# Orbiter_V2.net
KiCad netlist of a schematic drawn in EAGLE
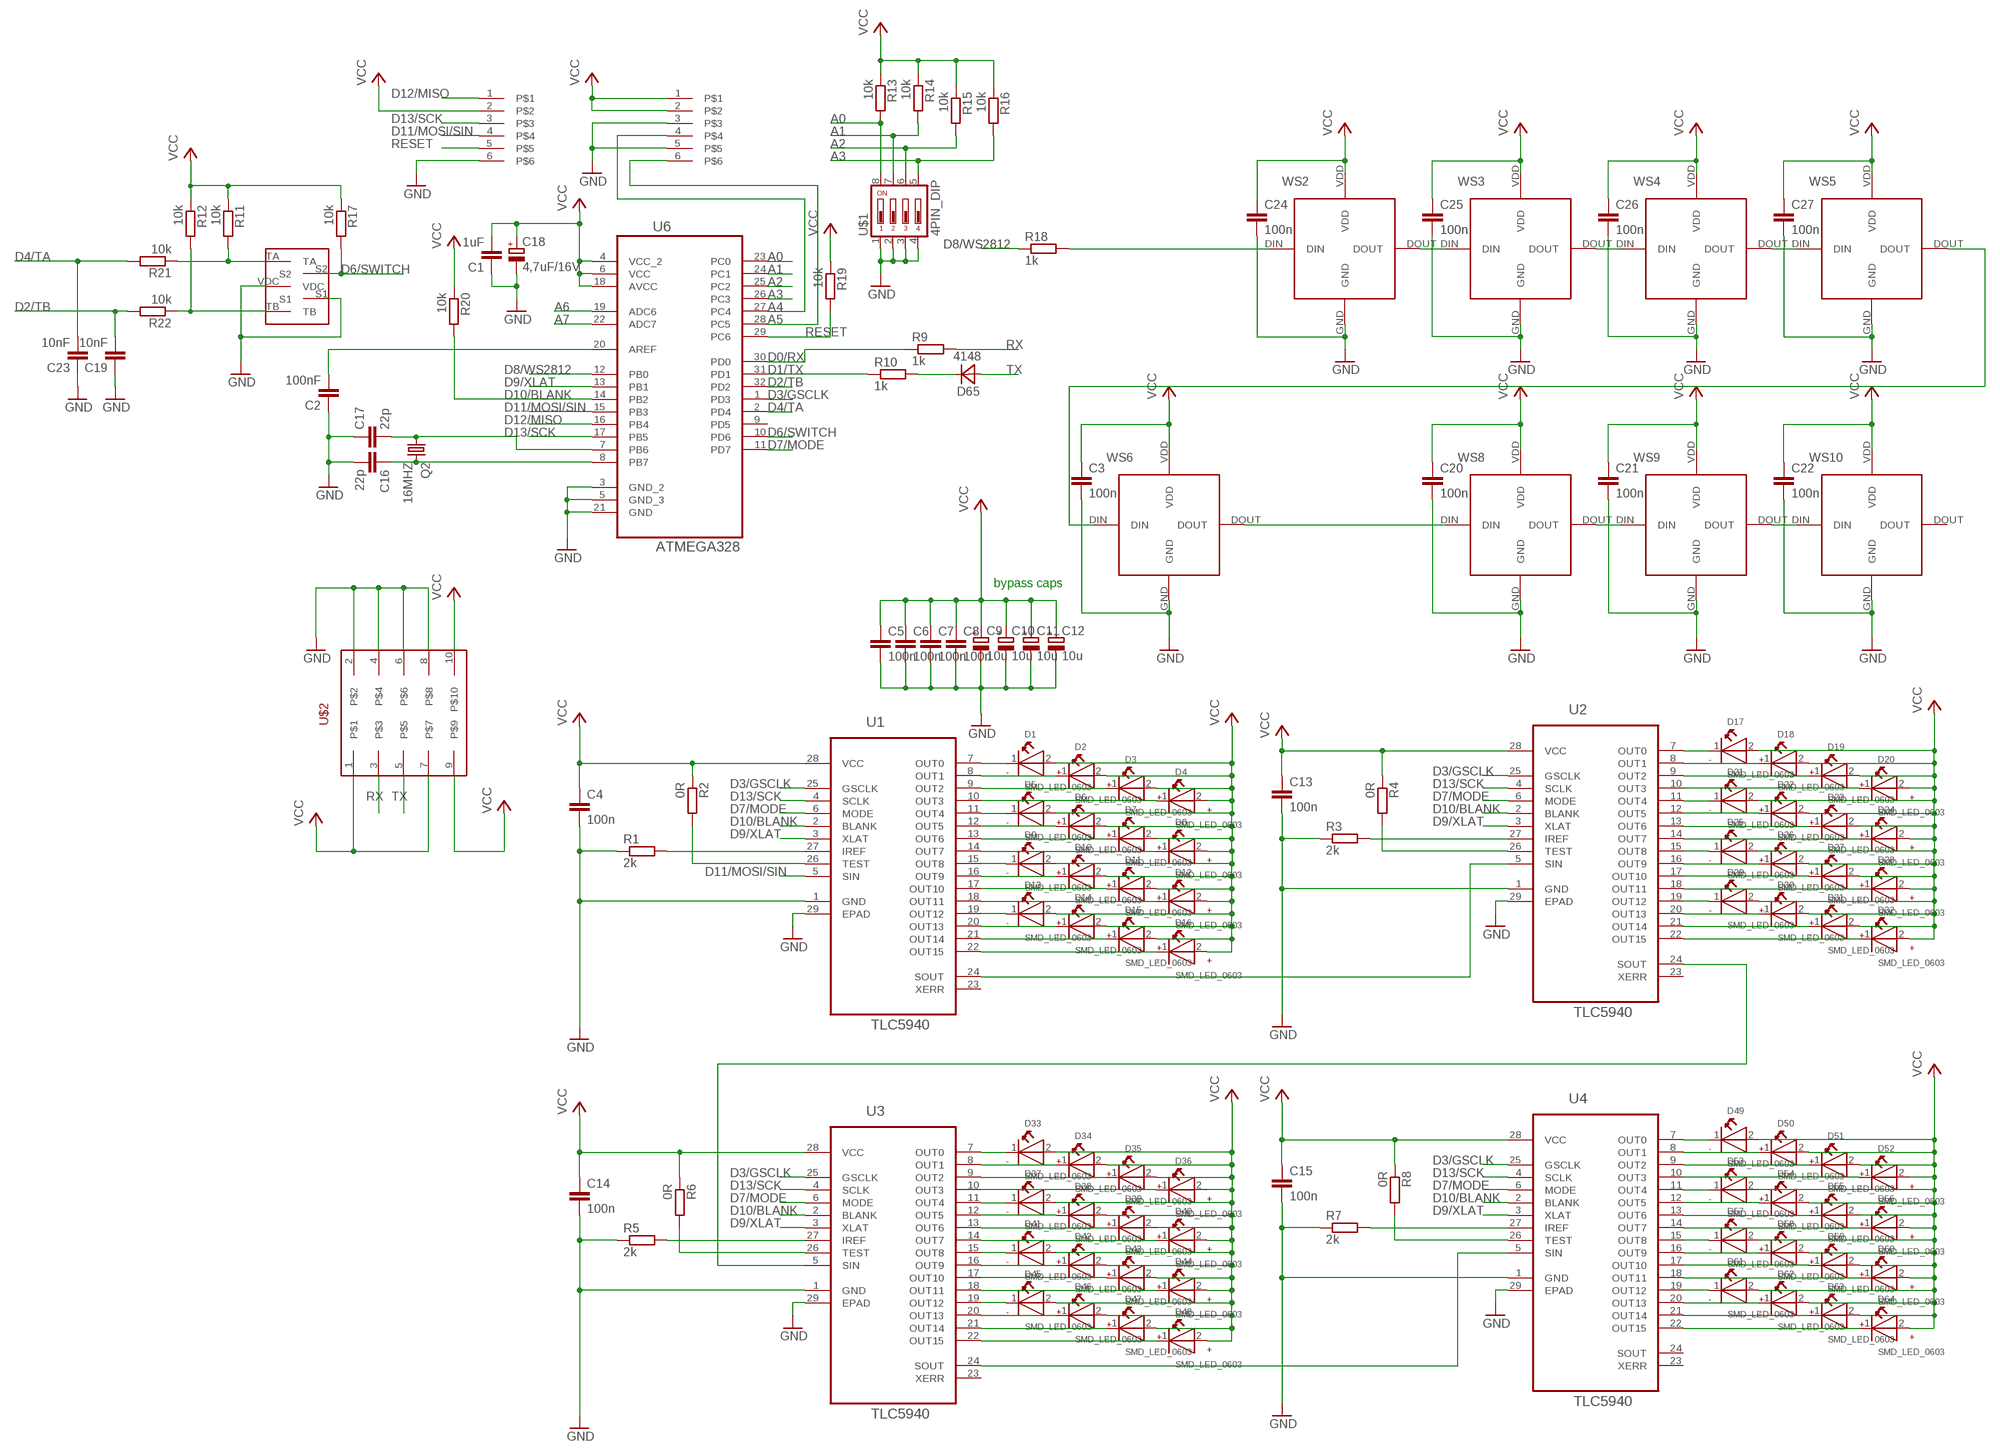
[diagram p0: schematic, sheet 1]

(export (version "E")
  (design (tool "Eeschema 10.0.6"))
  (components
    (comp (ref "C1")
      (value "1uF")
      (footprint "eagle-import:C0603")
      (libsource (lib "eagle-import") (part "KONDENSATOR_0603"))
    )
    (comp (ref "C2")
      (value "100nF")
      (footprint "eagle-import:C0603")
      (libsource (lib "eagle-import") (part "KONDENSATOR_0603"))
    )
    (comp (ref "C3")
      (value "100n")
      (footprint "eagle-import:C0603")
      (libsource (lib "eagle-import") (part "KONDENSATOR_0603"))
    )
    (comp (ref "C4")
      (value "100n")
      (footprint "eagle-import:C0603")
      (libsource (lib "eagle-import") (part "KONDENSATOR_0603"))
    )
    (comp (ref "C5")
      (value "100n")
      (footprint "eagle-import:C0603")
      (libsource (lib "eagle-import") (part "KONDENSATOR_0603"))
    )
    (comp (ref "C6")
      (value "100n")
      (footprint "eagle-import:C0603")
      (libsource (lib "eagle-import") (part "KONDENSATOR_0603"))
    )
    (comp (ref "C7")
      (value "100n")
      (footprint "eagle-import:C0603")
      (libsource (lib "eagle-import") (part "KONDENSATOR_0603"))
    )
    (comp (ref "C8")
      (value "100n")
      (footprint "eagle-import:C0603")
      (libsource (lib "eagle-import") (part "KONDENSATOR_0603"))
    )
    (comp (ref "C9")
      (value "10u")
      (footprint "eagle-import:153CLV-0605")
      (libsource (lib "eagle-import") (part "SMD_ELCTROLYTIC"))
    )
    (comp (ref "C10")
      (value "10u")
      (footprint "eagle-import:153CLV-0605")
      (libsource (lib "eagle-import") (part "SMD_ELCTROLYTIC"))
    )
    (comp (ref "C11")
      (value "10u")
      (footprint "eagle-import:153CLV-0605")
      (libsource (lib "eagle-import") (part "SMD_ELCTROLYTIC"))
    )
    (comp (ref "C12")
      (value "10u")
      (footprint "eagle-import:153CLV-0605")
      (libsource (lib "eagle-import") (part "SMD_ELCTROLYTIC"))
    )
    (comp (ref "C13")
      (value "100n")
      (footprint "eagle-import:C0603")
      (libsource (lib "eagle-import") (part "KONDENSATOR_0603"))
    )
    (comp (ref "C14")
      (value "100n")
      (footprint "eagle-import:C0603")
      (libsource (lib "eagle-import") (part "KONDENSATOR_0603"))
    )
    (comp (ref "C15")
      (value "100n")
      (footprint "eagle-import:C0603")
      (libsource (lib "eagle-import") (part "KONDENSATOR_0603"))
    )
    (comp (ref "C16")
      (value "22p")
      (footprint "eagle-import:C0603")
      (libsource (lib "eagle-import") (part "KONDENSATOR_0603"))
    )
    (comp (ref "C17")
      (value "22p")
      (footprint "eagle-import:C0603")
      (libsource (lib "eagle-import") (part "KONDENSATOR_0603"))
    )
    (comp (ref "C18")
      (value "4,7uF/16V")
      (footprint "eagle-import:153CLV-0605")
      (libsource (lib "eagle-import") (part "SMD_ELCTROLYTIC"))
    )
    (comp (ref "C19")
      (value "10nF")
      (footprint "eagle-import:C0603")
      (libsource (lib "eagle-import") (part "KONDENSATOR_0603"))
    )
    (comp (ref "C20")
      (value "100n")
      (footprint "eagle-import:C0603")
      (libsource (lib "eagle-import") (part "KONDENSATOR_0603"))
    )
    (comp (ref "C21")
      (value "100n")
      (footprint "eagle-import:C0603")
      (libsource (lib "eagle-import") (part "KONDENSATOR_0603"))
    )
    (comp (ref "C22")
      (value "100n")
      (footprint "eagle-import:C0603")
      (libsource (lib "eagle-import") (part "KONDENSATOR_0603"))
    )
    (comp (ref "C23")
      (value "10nF")
      (footprint "eagle-import:C0603")
      (libsource (lib "eagle-import") (part "KONDENSATOR_0603"))
    )
    (comp (ref "C24")
      (value "100n")
      (footprint "eagle-import:C0603")
      (libsource (lib "eagle-import") (part "KONDENSATOR_0603"))
    )
    (comp (ref "C25")
      (value "100n")
      (footprint "eagle-import:C0603")
      (libsource (lib "eagle-import") (part "KONDENSATOR_0603"))
    )
    (comp (ref "C26")
      (value "100n")
      (footprint "eagle-import:C0603")
      (libsource (lib "eagle-import") (part "KONDENSATOR_0603"))
    )
    (comp (ref "C27")
      (value "100n")
      (footprint "eagle-import:C0603")
      (libsource (lib "eagle-import") (part "KONDENSATOR_0603"))
    )
    (comp (ref "D1")
      (value "SMD_LED_0603")
      (footprint "eagle-import:WL-SMCW_0603")
      (libsource (lib "eagle-import") (part "SMD_LED_0603"))
    )
    (comp (ref "D2")
      (value "SMD_LED_0603")
      (footprint "eagle-import:WL-SMCW_0603")
      (libsource (lib "eagle-import") (part "SMD_LED_0603"))
    )
    (comp (ref "D3")
      (value "SMD_LED_0603")
      (footprint "eagle-import:WL-SMCW_0603")
      (libsource (lib "eagle-import") (part "SMD_LED_0603"))
    )
    (comp (ref "D4")
      (value "SMD_LED_0603")
      (footprint "eagle-import:WL-SMCW_0603")
      (libsource (lib "eagle-import") (part "SMD_LED_0603"))
    )
    (comp (ref "D5")
      (value "SMD_LED_0603")
      (footprint "eagle-import:WL-SMCW_0603")
      (libsource (lib "eagle-import") (part "SMD_LED_0603"))
    )
    (comp (ref "D6")
      (value "SMD_LED_0603")
      (footprint "eagle-import:WL-SMCW_0603")
      (libsource (lib "eagle-import") (part "SMD_LED_0603"))
    )
    (comp (ref "D7")
      (value "SMD_LED_0603")
      (footprint "eagle-import:WL-SMCW_0603")
      (libsource (lib "eagle-import") (part "SMD_LED_0603"))
    )
    (comp (ref "D8")
      (value "SMD_LED_0603")
      (footprint "eagle-import:WL-SMCW_0603")
      (libsource (lib "eagle-import") (part "SMD_LED_0603"))
    )
    (comp (ref "D9")
      (value "SMD_LED_0603")
      (footprint "eagle-import:WL-SMCW_0603")
      (libsource (lib "eagle-import") (part "SMD_LED_0603"))
    )
    (comp (ref "D10")
      (value "SMD_LED_0603")
      (footprint "eagle-import:WL-SMCW_0603")
      (libsource (lib "eagle-import") (part "SMD_LED_0603"))
    )
    (comp (ref "D11")
      (value "SMD_LED_0603")
      (footprint "eagle-import:WL-SMCW_0603")
      (libsource (lib "eagle-import") (part "SMD_LED_0603"))
    )
    (comp (ref "D12")
      (value "SMD_LED_0603")
      (footprint "eagle-import:WL-SMCW_0603")
      (libsource (lib "eagle-import") (part "SMD_LED_0603"))
    )
    (comp (ref "D13")
      (value "SMD_LED_0603")
      (footprint "eagle-import:WL-SMCW_0603")
      (libsource (lib "eagle-import") (part "SMD_LED_0603"))
    )
    (comp (ref "D14")
      (value "SMD_LED_0603")
      (footprint "eagle-import:WL-SMCW_0603")
      (libsource (lib "eagle-import") (part "SMD_LED_0603"))
    )
    (comp (ref "D15")
      (value "SMD_LED_0603")
      (footprint "eagle-import:WL-SMCW_0603")
      (libsource (lib "eagle-import") (part "SMD_LED_0603"))
    )
    (comp (ref "D16")
      (value "SMD_LED_0603")
      (footprint "eagle-import:WL-SMCW_0603")
      (libsource (lib "eagle-import") (part "SMD_LED_0603"))
    )
    (comp (ref "D17")
      (value "SMD_LED_0603")
      (footprint "eagle-import:WL-SMCW_0603")
      (libsource (lib "eagle-import") (part "SMD_LED_0603"))
    )
    (comp (ref "D18")
      (value "SMD_LED_0603")
      (footprint "eagle-import:WL-SMCW_0603")
      (libsource (lib "eagle-import") (part "SMD_LED_0603"))
    )
    (comp (ref "D19")
      (value "SMD_LED_0603")
      (footprint "eagle-import:WL-SMCW_0603")
      (libsource (lib "eagle-import") (part "SMD_LED_0603"))
    )
    (comp (ref "D20")
      (value "SMD_LED_0603")
      (footprint "eagle-import:WL-SMCW_0603")
      (libsource (lib "eagle-import") (part "SMD_LED_0603"))
    )
    (comp (ref "D21")
      (value "SMD_LED_0603")
      (footprint "eagle-import:WL-SMCW_0603")
      (libsource (lib "eagle-import") (part "SMD_LED_0603"))
    )
    (comp (ref "D22")
      (value "SMD_LED_0603")
      (footprint "eagle-import:WL-SMCW_0603")
      (libsource (lib "eagle-import") (part "SMD_LED_0603"))
    )
    (comp (ref "D23")
      (value "SMD_LED_0603")
      (footprint "eagle-import:WL-SMCW_0603")
      (libsource (lib "eagle-import") (part "SMD_LED_0603"))
    )
    (comp (ref "D24")
      (value "SMD_LED_0603")
      (footprint "eagle-import:WL-SMCW_0603")
      (libsource (lib "eagle-import") (part "SMD_LED_0603"))
    )
    (comp (ref "D25")
      (value "SMD_LED_0603")
      (footprint "eagle-import:WL-SMCW_0603")
      (libsource (lib "eagle-import") (part "SMD_LED_0603"))
    )
    (comp (ref "D26")
      (value "SMD_LED_0603")
      (footprint "eagle-import:WL-SMCW_0603")
      (libsource (lib "eagle-import") (part "SMD_LED_0603"))
    )
    (comp (ref "D27")
      (value "SMD_LED_0603")
      (footprint "eagle-import:WL-SMCW_0603")
      (libsource (lib "eagle-import") (part "SMD_LED_0603"))
    )
    (comp (ref "D28")
      (value "SMD_LED_0603")
      (footprint "eagle-import:WL-SMCW_0603")
      (libsource (lib "eagle-import") (part "SMD_LED_0603"))
    )
    (comp (ref "D29")
      (value "SMD_LED_0603")
      (footprint "eagle-import:WL-SMCW_0603")
      (libsource (lib "eagle-import") (part "SMD_LED_0603"))
    )
    (comp (ref "D30")
      (value "SMD_LED_0603")
      (footprint "eagle-import:WL-SMCW_0603")
      (libsource (lib "eagle-import") (part "SMD_LED_0603"))
    )
    (comp (ref "D31")
      (value "SMD_LED_0603")
      (footprint "eagle-import:WL-SMCW_0603")
      (libsource (lib "eagle-import") (part "SMD_LED_0603"))
    )
    (comp (ref "D32")
      (value "SMD_LED_0603")
      (footprint "eagle-import:WL-SMCW_0603")
      (libsource (lib "eagle-import") (part "SMD_LED_0603"))
    )
    (comp (ref "D33")
      (value "SMD_LED_0603")
      (footprint "eagle-import:WL-SMCW_0603")
      (libsource (lib "eagle-import") (part "SMD_LED_0603"))
    )
    (comp (ref "D34")
      (value "SMD_LED_0603")
      (footprint "eagle-import:WL-SMCW_0603")
      (libsource (lib "eagle-import") (part "SMD_LED_0603"))
    )
    (comp (ref "D35")
      (value "SMD_LED_0603")
      (footprint "eagle-import:WL-SMCW_0603")
      (libsource (lib "eagle-import") (part "SMD_LED_0603"))
    )
    (comp (ref "D36")
      (value "SMD_LED_0603")
      (footprint "eagle-import:WL-SMCW_0603")
      (libsource (lib "eagle-import") (part "SMD_LED_0603"))
    )
    (comp (ref "D37")
      (value "SMD_LED_0603")
      (footprint "eagle-import:WL-SMCW_0603")
      (libsource (lib "eagle-import") (part "SMD_LED_0603"))
    )
    (comp (ref "D38")
      (value "SMD_LED_0603")
      (footprint "eagle-import:WL-SMCW_0603")
      (libsource (lib "eagle-import") (part "SMD_LED_0603"))
    )
    (comp (ref "D39")
      (value "SMD_LED_0603")
      (footprint "eagle-import:WL-SMCW_0603")
      (libsource (lib "eagle-import") (part "SMD_LED_0603"))
    )
    (comp (ref "D40")
      (value "SMD_LED_0603")
      (footprint "eagle-import:WL-SMCW_0603")
      (libsource (lib "eagle-import") (part "SMD_LED_0603"))
    )
    (comp (ref "D41")
      (value "SMD_LED_0603")
      (footprint "eagle-import:WL-SMCW_0603")
      (libsource (lib "eagle-import") (part "SMD_LED_0603"))
    )
    (comp (ref "D42")
      (value "SMD_LED_0603")
      (footprint "eagle-import:WL-SMCW_0603")
      (libsource (lib "eagle-import") (part "SMD_LED_0603"))
    )
    (comp (ref "D43")
      (value "SMD_LED_0603")
      (footprint "eagle-import:WL-SMCW_0603")
      (libsource (lib "eagle-import") (part "SMD_LED_0603"))
    )
    (comp (ref "D44")
      (value "SMD_LED_0603")
      (footprint "eagle-import:WL-SMCW_0603")
      (libsource (lib "eagle-import") (part "SMD_LED_0603"))
    )
    (comp (ref "D45")
      (value "SMD_LED_0603")
      (footprint "eagle-import:WL-SMCW_0603")
      (libsource (lib "eagle-import") (part "SMD_LED_0603"))
    )
    (comp (ref "D46")
      (value "SMD_LED_0603")
      (footprint "eagle-import:WL-SMCW_0603")
      (libsource (lib "eagle-import") (part "SMD_LED_0603"))
    )
    (comp (ref "D47")
      (value "SMD_LED_0603")
      (footprint "eagle-import:WL-SMCW_0603")
      (libsource (lib "eagle-import") (part "SMD_LED_0603"))
    )
    (comp (ref "D48")
      (value "SMD_LED_0603")
      (footprint "eagle-import:WL-SMCW_0603")
      (libsource (lib "eagle-import") (part "SMD_LED_0603"))
    )
    (comp (ref "D49")
      (value "SMD_LED_0603")
      (footprint "eagle-import:WL-SMCW_0603")
      (libsource (lib "eagle-import") (part "SMD_LED_0603"))
    )
    (comp (ref "D50")
      (value "SMD_LED_0603")
      (footprint "eagle-import:WL-SMCW_0603")
      (libsource (lib "eagle-import") (part "SMD_LED_0603"))
    )
    (comp (ref "D51")
      (value "SMD_LED_0603")
      (footprint "eagle-import:WL-SMCW_0603")
      (libsource (lib "eagle-import") (part "SMD_LED_0603"))
    )
    (comp (ref "D52")
      (value "SMD_LED_0603")
      (footprint "eagle-import:WL-SMCW_0603")
      (libsource (lib "eagle-import") (part "SMD_LED_0603"))
    )
    (comp (ref "D53")
      (value "SMD_LED_0603")
      (footprint "eagle-import:WL-SMCW_0603")
      (libsource (lib "eagle-import") (part "SMD_LED_0603"))
    )
    (comp (ref "D54")
      (value "SMD_LED_0603")
      (footprint "eagle-import:WL-SMCW_0603")
      (libsource (lib "eagle-import") (part "SMD_LED_0603"))
    )
    (comp (ref "D55")
      (value "SMD_LED_0603")
      (footprint "eagle-import:WL-SMCW_0603")
      (libsource (lib "eagle-import") (part "SMD_LED_0603"))
    )
    (comp (ref "D56")
      (value "SMD_LED_0603")
      (footprint "eagle-import:WL-SMCW_0603")
      (libsource (lib "eagle-import") (part "SMD_LED_0603"))
    )
    (comp (ref "D57")
      (value "SMD_LED_0603")
      (footprint "eagle-import:WL-SMCW_0603")
      (libsource (lib "eagle-import") (part "SMD_LED_0603"))
    )
    (comp (ref "D58")
      (value "SMD_LED_0603")
      (footprint "eagle-import:WL-SMCW_0603")
      (libsource (lib "eagle-import") (part "SMD_LED_0603"))
    )
    (comp (ref "D59")
      (value "SMD_LED_0603")
      (footprint "eagle-import:WL-SMCW_0603")
      (libsource (lib "eagle-import") (part "SMD_LED_0603"))
    )
    (comp (ref "D60")
      (value "SMD_LED_0603")
      (footprint "eagle-import:WL-SMCW_0603")
      (libsource (lib "eagle-import") (part "SMD_LED_0603"))
    )
    (comp (ref "D61")
      (value "SMD_LED_0603")
      (footprint "eagle-import:WL-SMCW_0603")
      (libsource (lib "eagle-import") (part "SMD_LED_0603"))
    )
    (comp (ref "D62")
      (value "SMD_LED_0603")
      (footprint "eagle-import:WL-SMCW_0603")
      (libsource (lib "eagle-import") (part "SMD_LED_0603"))
    )
    (comp (ref "D63")
      (value "SMD_LED_0603")
      (footprint "eagle-import:WL-SMCW_0603")
      (libsource (lib "eagle-import") (part "SMD_LED_0603"))
    )
    (comp (ref "D64")
      (value "SMD_LED_0603")
      (footprint "eagle-import:WL-SMCW_0603")
      (libsource (lib "eagle-import") (part "SMD_LED_0603"))
    )
    (comp (ref "D65")
      (value "4148")
      (footprint "eagle-import:SOD323-R")
      (libsource (lib "eagle-import") (part "4148_SOD323"))
    )
    (comp (ref "Q2")
      (value "16MHZ")
      (footprint "eagle-import:SM49")
      (libsource (lib "eagle-import") (part "CRYSTAL_SM49"))
    )
    (comp (ref "R1")
      (value "2k")
      (footprint "eagle-import:R0805")
      (libsource (lib "eagle-import") (part "WIDERSTAND_0805R0805"))
    )
    (comp (ref "R2")
      (value "0R")
      (footprint "eagle-import:R0805")
      (libsource (lib "eagle-import") (part "WIDERSTAND_0805R0805"))
    )
    (comp (ref "R3")
      (value "2k")
      (footprint "eagle-import:R0805")
      (libsource (lib "eagle-import") (part "WIDERSTAND_0805R0805"))
    )
    (comp (ref "R4")
      (value "0R")
      (footprint "eagle-import:R0805")
      (libsource (lib "eagle-import") (part "WIDERSTAND_0805R0805"))
    )
    (comp (ref "R5")
      (value "2k")
      (footprint "eagle-import:R0805")
      (libsource (lib "eagle-import") (part "WIDERSTAND_0805R0805"))
    )
    (comp (ref "R6")
      (value "0R")
      (footprint "eagle-import:R0805")
      (libsource (lib "eagle-import") (part "WIDERSTAND_0805R0805"))
    )
    (comp (ref "R7")
      (value "2k")
      (footprint "eagle-import:R0805")
      (libsource (lib "eagle-import") (part "WIDERSTAND_0805R0805"))
    )
    (comp (ref "R8")
      (value "0R")
      (footprint "eagle-import:R0805")
      (libsource (lib "eagle-import") (part "WIDERSTAND_0805R0805"))
    )
    (comp (ref "R9")
      (value "1k")
      (footprint "eagle-import:R0805")
      (libsource (lib "eagle-import") (part "WIDERSTAND_0805R0805"))
    )
    (comp (ref "R10")
      (value "1k")
      (footprint "eagle-import:R0805")
      (libsource (lib "eagle-import") (part "WIDERSTAND_0805R0805"))
    )
    (comp (ref "R11")
      (value "10k")
      (footprint "eagle-import:R0805")
      (libsource (lib "eagle-import") (part "WIDERSTAND_0805R0805"))
    )
    (comp (ref "R12")
      (value "10k")
      (footprint "eagle-import:R0805")
      (libsource (lib "eagle-import") (part "WIDERSTAND_0805R0805"))
    )
    (comp (ref "R13")
      (value "10k")
      (footprint "eagle-import:R0805")
      (libsource (lib "eagle-import") (part "WIDERSTAND_0805R0805"))
    )
    (comp (ref "R14")
      (value "10k")
      (footprint "eagle-import:R0805")
      (libsource (lib "eagle-import") (part "WIDERSTAND_0805R0805"))
    )
    (comp (ref "R15")
      (value "10k")
      (footprint "eagle-import:R0805")
      (libsource (lib "eagle-import") (part "WIDERSTAND_0805R0805"))
    )
    (comp (ref "R16")
      (value "10k")
      (footprint "eagle-import:R0805")
      (libsource (lib "eagle-import") (part "WIDERSTAND_0805R0805"))
    )
    (comp (ref "R17")
      (value "10k")
      (footprint "eagle-import:R0805")
      (libsource (lib "eagle-import") (part "WIDERSTAND_0805R0805"))
    )
    (comp (ref "R18")
      (value "1k")
      (footprint "eagle-import:R0805")
      (libsource (lib "eagle-import") (part "WIDERSTAND_0805R0805"))
    )
    (comp (ref "R19")
      (value "10k")
      (footprint "eagle-import:R0805")
      (libsource (lib "eagle-import") (part "WIDERSTAND_0805R0805"))
    )
    (comp (ref "R20")
      (value "10k")
      (footprint "eagle-import:R0805")
      (libsource (lib "eagle-import") (part "WIDERSTAND_0805R0805"))
    )
    (comp (ref "R21")
      (value "10k")
      (footprint "eagle-import:R0805")
      (libsource (lib "eagle-import") (part "WIDERSTAND_0805R0805"))
    )
    (comp (ref "R22")
      (value "10k")
      (footprint "eagle-import:R0805")
      (libsource (lib "eagle-import") (part "WIDERSTAND_0805R0805"))
    )
    (comp (ref "U$1")
      (value "4PIN_DIP")
      (footprint "eagle-import:CTS-219-04")
      (libsource (lib "eagle-import") (part "4PIN_DIP"))
    )
    (comp (ref "U$2")
      (value "10PIN_HEADER_SMD")
      (footprint "eagle-import:87832-10")
      (libsource (lib "eagle-import") (part "10PIN_HEADER_SMD"))
    )
    (comp (ref "U$3")
      (value "6PIN_HEADER_SMD_OPEN")
      (footprint "eagle-import:6PIN_HEADER_SMD_OPEN")
      (libsource (lib "eagle-import") (part "6PIN_HEADER_SMD_OPEN"))
    )
    (comp (ref "U$4")
      (value "BOURNS_ENCODER")
      (footprint "eagle-import:BOURNS_ENCODER_SMD")
      (libsource (lib "eagle-import") (part "BOURNS_ENCODER"))
    )
    (comp (ref "U$5")
      (value "6PIN_HEADER_SMD_OPEN")
      (footprint "eagle-import:6PIN_HEADER_SMD_OPEN")
      (libsource (lib "eagle-import") (part "6PIN_HEADER_SMD_OPEN"))
    )
    (comp (ref "U1")
      (value "TLC5940")
      (footprint "eagle-import:SOP65P640X120-29N")
      (fields (field (name "MPN") "TLC59401PWP"))
      (libsource (lib "eagle-import") (part "TLC59401PWP"))
    )
    (comp (ref "U2")
      (value "TLC5940")
      (footprint "eagle-import:SOP65P640X120-29N")
      (fields (field (name "MPN") "TLC59401PWP"))
      (libsource (lib "eagle-import") (part "TLC59401PWP"))
    )
    (comp (ref "U3")
      (value "TLC5940")
      (footprint "eagle-import:SOP65P640X120-29N")
      (fields (field (name "MPN") "TLC59401PWP"))
      (libsource (lib "eagle-import") (part "TLC59401PWP"))
    )
    (comp (ref "U4")
      (value "TLC5940")
      (footprint "eagle-import:SOP65P640X120-29N")
      (fields (field (name "MPN") "TLC59401PWP"))
      (libsource (lib "eagle-import") (part "TLC59401PWP"))
    )
    (comp (ref "U6")
      (value "ATMEGA328")
      (footprint "eagle-import:QFP80P900X900X120-32N")
      (fields (field (name "MPN") "ATMEGA328P-AU"))
      (libsource (lib "eagle-import") (part "ATMEGA328P-AU"))
    )
    (comp (ref "WS2")
      (value "WS2812")
      (footprint "eagle-import:WS2812")
      (libsource (lib "eagle-import") (part "WS2812"))
    )
    (comp (ref "WS3")
      (value "WS2812")
      (footprint "eagle-import:WS2812")
      (libsource (lib "eagle-import") (part "WS2812"))
    )
    (comp (ref "WS4")
      (value "WS2812")
      (footprint "eagle-import:WS2812")
      (libsource (lib "eagle-import") (part "WS2812"))
    )
    (comp (ref "WS5")
      (value "WS2812")
      (footprint "eagle-import:WS2812")
      (libsource (lib "eagle-import") (part "WS2812"))
    )
    (comp (ref "WS6")
      (value "WS2812")
      (footprint "eagle-import:WS2812")
      (libsource (lib "eagle-import") (part "WS2812"))
    )
    (comp (ref "WS8")
      (value "WS2812")
      (footprint "eagle-import:WS2812")
      (libsource (lib "eagle-import") (part "WS2812"))
    )
    (comp (ref "WS9")
      (value "WS2812")
      (footprint "eagle-import:WS2812")
      (libsource (lib "eagle-import") (part "WS2812"))
    )
    (comp (ref "WS10")
      (value "WS2812")
      (footprint "eagle-import:WS2812")
      (libsource (lib "eagle-import") (part "WS2812"))
    )
  )
  (nets
    (net (code "1") (name "/A0") (class "Default")
      (node (ref "R13") (pin "2") (pinfunction "2_2") (pintype "passive"))
      (node (ref "U$1") (pin "8") (pinfunction "8_8") (pintype "passive"))
      (node (ref "U6") (pin "23") (pinfunction "PC0_23") (pintype "bidirectional"))
    )
    (net (code "2") (name "/A1") (class "Default")
      (node (ref "R14") (pin "2") (pinfunction "2_2") (pintype "passive"))
      (node (ref "U$1") (pin "7") (pinfunction "7_7") (pintype "passive"))
      (node (ref "U6") (pin "24") (pinfunction "PC1_24") (pintype "bidirectional"))
    )
    (net (code "3") (name "/A2") (class "Default")
      (node (ref "R15") (pin "2") (pinfunction "2_2") (pintype "passive"))
      (node (ref "U$1") (pin "6") (pinfunction "6_6") (pintype "passive"))
      (node (ref "U6") (pin "25") (pinfunction "PC2_25") (pintype "bidirectional"))
    )
    (net (code "4") (name "/A3") (class "Default")
      (node (ref "R16") (pin "2") (pinfunction "2_2") (pintype "passive"))
      (node (ref "U$1") (pin "5") (pinfunction "5_5") (pintype "passive"))
      (node (ref "U6") (pin "26") (pinfunction "PC3_26") (pintype "bidirectional"))
    )
    (net (code "5") (name "/A4") (class "Default")
      (node (ref "U$5") (pin "4") (pinfunction "P$4_4") (pintype "bidirectional"))
      (node (ref "U6") (pin "27") (pinfunction "PC4_27") (pintype "bidirectional"))
    )
    (net (code "6") (name "/A5") (class "Default")
      (node (ref "U$5") (pin "6") (pinfunction "P$6_6") (pintype "bidirectional"))
      (node (ref "U6") (pin "28") (pinfunction "PC5_28") (pintype "bidirectional"))
    )
    (net (code "7") (name "/A6") (class "Default")
      (node (ref "U6") (pin "19") (pinfunction "ADC6_19") (pintype "input"))
    )
    (net (code "8") (name "/A7") (class "Default")
      (node (ref "U6") (pin "22") (pinfunction "ADC7_22") (pintype "input"))
    )
    (net (code "9") (name "/D0{slash}RX") (class "Default")
      (node (ref "R9") (pin "1") (pinfunction "1_1") (pintype "passive"))
      (node (ref "U6") (pin "30") (pinfunction "PD0_30") (pintype "bidirectional"))
    )
    (net (code "10") (name "/D1{slash}TX") (class "Default")
      (node (ref "R10") (pin "1") (pinfunction "1_1") (pintype "passive"))
      (node (ref "U6") (pin "31") (pinfunction "PD1_31") (pintype "bidirectional"))
    )
    (net (code "11") (name "/D2{slash}TB") (class "Default")
      (node (ref "C19") (pin "2") (pinfunction "2_2") (pintype "passive"))
      (node (ref "R22") (pin "2") (pinfunction "2_2") (pintype "passive"))
      (node (ref "U6") (pin "32") (pinfunction "PD2_32") (pintype "bidirectional"))
    )
    (net (code "12") (name "/D3{slash}GSCLK") (class "Default")
      (node (ref "U1") (pin "25") (pinfunction "GSCLK_25") (pintype "input"))
      (node (ref "U2") (pin "25") (pinfunction "GSCLK_25") (pintype "input"))
      (node (ref "U3") (pin "25") (pinfunction "GSCLK_25") (pintype "input"))
      (node (ref "U4") (pin "25") (pinfunction "GSCLK_25") (pintype "input"))
      (node (ref "U6") (pin "1") (pinfunction "PD3_1") (pintype "bidirectional"))
    )
    (net (code "13") (name "/D4{slash}TA") (class "Default")
      (node (ref "C23") (pin "2") (pinfunction "2_2") (pintype "passive"))
      (node (ref "R21") (pin "2") (pinfunction "2_2") (pintype "passive"))
      (node (ref "U6") (pin "2") (pinfunction "PD4_2") (pintype "bidirectional"))
    )
    (net (code "14") (name "/D6{slash}SWITCH") (class "Default")
      (node (ref "R17") (pin "2") (pinfunction "2_2") (pintype "passive"))
      (node (ref "U$4") (pin "S2") (pinfunction "S2_S2") (pintype "bidirectional"))
      (node (ref "U6") (pin "10") (pinfunction "PD6_10") (pintype "bidirectional"))
    )
    (net (code "15") (name "/D7{slash}MODE") (class "Default")
      (node (ref "U1") (pin "6") (pinfunction "MODE_6") (pintype "input"))
      (node (ref "U2") (pin "6") (pinfunction "MODE_6") (pintype "input"))
      (node (ref "U3") (pin "6") (pinfunction "MODE_6") (pintype "input"))
      (node (ref "U4") (pin "6") (pinfunction "MODE_6") (pintype "input"))
      (node (ref "U6") (pin "11") (pinfunction "PD7_11") (pintype "bidirectional"))
    )
    (net (code "16") (name "/D8{slash}WS2812") (class "Default")
      (node (ref "R18") (pin "1") (pinfunction "1_1") (pintype "passive"))
      (node (ref "U6") (pin "12") (pinfunction "PB0_12") (pintype "bidirectional"))
    )
    (net (code "17") (name "/D9{slash}XLAT") (class "Default")
      (node (ref "U1") (pin "3") (pinfunction "XLAT_3") (pintype "input"))
      (node (ref "U2") (pin "3") (pinfunction "XLAT_3") (pintype "input"))
      (node (ref "U3") (pin "3") (pinfunction "XLAT_3") (pintype "input"))
      (node (ref "U4") (pin "3") (pinfunction "XLAT_3") (pintype "input"))
      (node (ref "U6") (pin "13") (pinfunction "PB1_13") (pintype "bidirectional"))
    )
    (net (code "18") (name "/D10{slash}BLANK") (class "Default")
      (node (ref "R20") (pin "2") (pinfunction "2_2") (pintype "passive"))
      (node (ref "U1") (pin "2") (pinfunction "BLANK_2") (pintype "input"))
      (node (ref "U2") (pin "2") (pinfunction "BLANK_2") (pintype "input"))
      (node (ref "U3") (pin "2") (pinfunction "BLANK_2") (pintype "input"))
      (node (ref "U4") (pin "2") (pinfunction "BLANK_2") (pintype "input"))
      (node (ref "U6") (pin "14") (pinfunction "PB2_14") (pintype "bidirectional"))
    )
    (net (code "19") (name "/D11{slash}MOSI{slash}SIN") (class "Default")
      (node (ref "U$3") (pin "4") (pinfunction "P$4_4") (pintype "bidirectional"))
      (node (ref "U1") (pin "5") (pinfunction "SIN_5") (pintype "input"))
      (node (ref "U6") (pin "15") (pinfunction "PB3_15") (pintype "bidirectional"))
    )
    (net (code "20") (name "/D12{slash}MISO") (class "Default")
      (node (ref "U$3") (pin "1") (pinfunction "P$1_1") (pintype "bidirectional"))
      (node (ref "U6") (pin "16") (pinfunction "PB4_16") (pintype "bidirectional"))
    )
    (net (code "21") (name "/D13{slash}SCK") (class "Default")
      (node (ref "U$3") (pin "3") (pinfunction "P$3_3") (pintype "bidirectional"))
      (node (ref "U1") (pin "4") (pinfunction "SCLK_4") (pintype "input"))
      (node (ref "U2") (pin "4") (pinfunction "SCLK_4") (pintype "input"))
      (node (ref "U3") (pin "4") (pinfunction "SCLK_4") (pintype "input"))
      (node (ref "U4") (pin "4") (pinfunction "SCLK_4") (pintype "input"))
      (node (ref "U6") (pin "17") (pinfunction "PB5_17") (pintype "bidirectional"))
    )
    (net (code "22") (name "/RESET") (class "Default")
      (node (ref "R19") (pin "2") (pinfunction "2_2") (pintype "passive"))
      (node (ref "U$3") (pin "5") (pinfunction "P$5_5") (pintype "bidirectional"))
      (node (ref "U6") (pin "29") (pinfunction "PC6_29") (pintype "bidirectional"))
    )
    (net (code "23") (name "/RX") (class "Default")
      (node (ref "R9") (pin "2") (pinfunction "2_2") (pintype "passive"))
      (node (ref "U$2") (pin "3") (pinfunction "P$3_3") (pintype "bidirectional"))
    )
    (net (code "24") (name "/TX") (class "Default")
      (node (ref "D65") (pin "A") (pinfunction "A_A") (pintype "passive"))
      (node (ref "U$2") (pin "5") (pinfunction "P$5_5") (pintype "bidirectional"))
    )
    (net (code "25") (name "GND") (class "Default")
      (node (ref "C1") (pin "1") (pinfunction "1_1") (pintype "passive"))
      (node (ref "C10") (pin "-") (pinfunction "-_-") (pintype "passive"))
      (node (ref "C11") (pin "-") (pinfunction "-_-") (pintype "passive"))
      (node (ref "C12") (pin "-") (pinfunction "-_-") (pintype "passive"))
      (node (ref "C13") (pin "2") (pinfunction "2_2") (pintype "passive"))
      (node (ref "C14") (pin "2") (pinfunction "2_2") (pintype "passive"))
      (node (ref "C15") (pin "2") (pinfunction "2_2") (pintype "passive"))
      (node (ref "C16") (pin "2") (pinfunction "2_2") (pintype "passive"))
      (node (ref "C17") (pin "1") (pinfunction "1_1") (pintype "passive"))
      (node (ref "C18") (pin "-") (pinfunction "-_-") (pintype "passive"))
      (node (ref "C19") (pin "1") (pinfunction "1_1") (pintype "passive"))
      (node (ref "C2") (pin "1") (pinfunction "1_1") (pintype "passive"))
      (node (ref "C20") (pin "2") (pinfunction "2_2") (pintype "passive"))
      (node (ref "C21") (pin "2") (pinfunction "2_2") (pintype "passive"))
      (node (ref "C22") (pin "2") (pinfunction "2_2") (pintype "passive"))
      (node (ref "C23") (pin "1") (pinfunction "1_1") (pintype "passive"))
      (node (ref "C24") (pin "2") (pinfunction "2_2") (pintype "passive"))
      (node (ref "C25") (pin "2") (pinfunction "2_2") (pintype "passive"))
      (node (ref "C26") (pin "2") (pinfunction "2_2") (pintype "passive"))
      (node (ref "C27") (pin "2") (pinfunction "2_2") (pintype "passive"))
      (node (ref "C3") (pin "2") (pinfunction "2_2") (pintype "passive"))
      (node (ref "C4") (pin "2") (pinfunction "2_2") (pintype "passive"))
      (node (ref "C5") (pin "2") (pinfunction "2_2") (pintype "passive"))
      (node (ref "C6") (pin "2") (pinfunction "2_2") (pintype "passive"))
      (node (ref "C7") (pin "2") (pinfunction "2_2") (pintype "passive"))
      (node (ref "C8") (pin "2") (pinfunction "2_2") (pintype "passive"))
      (node (ref "C9") (pin "-") (pinfunction "-_-") (pintype "passive"))
      (node (ref "R1") (pin "1") (pinfunction "1_1") (pintype "passive"))
      (node (ref "R3") (pin "1") (pinfunction "1_1") (pintype "passive"))
      (node (ref "R5") (pin "1") (pinfunction "1_1") (pintype "passive"))
      (node (ref "R7") (pin "1") (pinfunction "1_1") (pintype "passive"))
      (node (ref "U$1") (pin "1") (pinfunction "1_1") (pintype "passive"))
      (node (ref "U$1") (pin "2") (pinfunction "2_2") (pintype "passive"))
      (node (ref "U$1") (pin "3") (pinfunction "3_3") (pintype "passive"))
      (node (ref "U$1") (pin "4") (pinfunction "4_4") (pintype "passive"))
      (node (ref "U$2") (pin "2") (pinfunction "P$2_2") (pintype "bidirectional"))
      (node (ref "U$2") (pin "4") (pinfunction "P$4_4") (pintype "bidirectional"))
      (node (ref "U$2") (pin "6") (pinfunction "P$6_6") (pintype "bidirectional"))
      (node (ref "U$2") (pin "8") (pinfunction "P$8_8") (pintype "bidirectional"))
      (node (ref "U$3") (pin "6") (pinfunction "P$6_6") (pintype "bidirectional"))
      (node (ref "U$4") (pin "S1") (pinfunction "S1_S1") (pintype "bidirectional"))
      (node (ref "U$4") (pin "VDC") (pinfunction "VDC_VDC") (pintype "bidirectional"))
      (node (ref "U$5") (pin "3") (pinfunction "P$3_3") (pintype "bidirectional"))
      (node (ref "U$5") (pin "5") (pinfunction "P$5_5") (pintype "bidirectional"))
      (node (ref "U1") (pin "1") (pinfunction "GND_1") (pintype "passive"))
      (node (ref "U1") (pin "29") (pinfunction "EPAD_29") (pintype "passive"))
      (node (ref "U2") (pin "1") (pinfunction "GND_1") (pintype "passive"))
      (node (ref "U2") (pin "29") (pinfunction "EPAD_29") (pintype "passive"))
      (node (ref "U3") (pin "1") (pinfunction "GND_1") (pintype "passive"))
      (node (ref "U3") (pin "29") (pinfunction "EPAD_29") (pintype "passive"))
      (node (ref "U4") (pin "1") (pinfunction "GND_1") (pintype "passive"))
      (node (ref "U4") (pin "29") (pinfunction "EPAD_29") (pintype "passive"))
      (node (ref "U6") (pin "21") (pinfunction "GND_21") (pintype "passive"))
      (node (ref "U6") (pin "3") (pinfunction "GND_2_3") (pintype "passive"))
      (node (ref "U6") (pin "5") (pinfunction "GND_3_5") (pintype "passive"))
      (node (ref "WS10") (pin "GND") (pinfunction "GND_GND") (pintype "bidirectional"))
      (node (ref "WS2") (pin "GND") (pinfunction "GND_GND") (pintype "bidirectional"))
      (node (ref "WS3") (pin "GND") (pinfunction "GND_GND") (pintype "bidirectional"))
      (node (ref "WS4") (pin "GND") (pinfunction "GND_GND") (pintype "bidirectional"))
      (node (ref "WS5") (pin "GND") (pinfunction "GND_GND") (pintype "bidirectional"))
      (node (ref "WS6") (pin "GND") (pinfunction "GND_GND") (pintype "bidirectional"))
      (node (ref "WS8") (pin "GND") (pinfunction "GND_GND") (pintype "bidirectional"))
      (node (ref "WS9") (pin "GND") (pinfunction "GND_GND") (pintype "bidirectional"))
    )
    (net (code "26") (name "Net-(D1--)") (class "Default")
      (node (ref "D1") (pin "1") (pinfunction "-_1") (pintype "passive"))
      (node (ref "U1") (pin "7") (pinfunction "OUT0_7") (pintype "output"))
    )
    (net (code "27") (name "Net-(D2--)") (class "Default")
      (node (ref "D2") (pin "1") (pinfunction "-_1") (pintype "passive"))
      (node (ref "U1") (pin "8") (pinfunction "OUT1_8") (pintype "output"))
    )
    (net (code "28") (name "Net-(D3--)") (class "Default")
      (node (ref "D3") (pin "1") (pinfunction "-_1") (pintype "passive"))
      (node (ref "U1") (pin "9") (pinfunction "OUT2_9") (pintype "output"))
    )
    (net (code "29") (name "Net-(D4--)") (class "Default")
      (node (ref "D4") (pin "1") (pinfunction "-_1") (pintype "passive"))
      (node (ref "U1") (pin "10") (pinfunction "OUT3_10") (pintype "output"))
    )
    (net (code "30") (name "Net-(D5--)") (class "Default")
      (node (ref "D5") (pin "1") (pinfunction "-_1") (pintype "passive"))
      (node (ref "U1") (pin "11") (pinfunction "OUT4_11") (pintype "output"))
    )
    (net (code "31") (name "Net-(D6--)") (class "Default")
      (node (ref "D6") (pin "1") (pinfunction "-_1") (pintype "passive"))
      (node (ref "U1") (pin "12") (pinfunction "OUT5_12") (pintype "output"))
    )
    (net (code "32") (name "Net-(D7--)") (class "Default")
      (node (ref "D7") (pin "1") (pinfunction "-_1") (pintype "passive"))
      (node (ref "U1") (pin "13") (pinfunction "OUT6_13") (pintype "output"))
    )
    (net (code "33") (name "Net-(D8--)") (class "Default")
      (node (ref "D8") (pin "1") (pinfunction "-_1") (pintype "passive"))
      (node (ref "U1") (pin "14") (pinfunction "OUT7_14") (pintype "output"))
    )
    (net (code "34") (name "Net-(D9--)") (class "Default")
      (node (ref "D9") (pin "1") (pinfunction "-_1") (pintype "passive"))
      (node (ref "U1") (pin "15") (pinfunction "OUT8_15") (pintype "output"))
    )
    (net (code "35") (name "Net-(D10--)") (class "Default")
      (node (ref "D10") (pin "1") (pinfunction "-_1") (pintype "passive"))
      (node (ref "U1") (pin "16") (pinfunction "OUT9_16") (pintype "output"))
    )
    (net (code "36") (name "Net-(D11--)") (class "Default")
      (node (ref "D11") (pin "1") (pinfunction "-_1") (pintype "passive"))
      (node (ref "U1") (pin "17") (pinfunction "OUT10_17") (pintype "output"))
    )
    (net (code "37") (name "Net-(D12--)") (class "Default")
      (node (ref "D12") (pin "1") (pinfunction "-_1") (pintype "passive"))
      (node (ref "U1") (pin "18") (pinfunction "OUT11_18") (pintype "output"))
    )
    (net (code "38") (name "Net-(D13--)") (class "Default")
      (node (ref "D13") (pin "1") (pinfunction "-_1") (pintype "passive"))
      (node (ref "U1") (pin "19") (pinfunction "OUT12_19") (pintype "output"))
    )
    (net (code "39") (name "Net-(D14--)") (class "Default")
      (node (ref "D14") (pin "1") (pinfunction "-_1") (pintype "passive"))
      (node (ref "U1") (pin "20") (pinfunction "OUT13_20") (pintype "output"))
    )
    (net (code "40") (name "Net-(D15--)") (class "Default")
      (node (ref "D15") (pin "1") (pinfunction "-_1") (pintype "passive"))
      (node (ref "U1") (pin "21") (pinfunction "OUT14_21") (pintype "output"))
    )
    (net (code "41") (name "Net-(D16--)") (class "Default")
      (node (ref "D16") (pin "1") (pinfunction "-_1") (pintype "passive"))
      (node (ref "U1") (pin "22") (pinfunction "OUT15_22") (pintype "output"))
    )
    (net (code "42") (name "Net-(D17--)") (class "Default")
      (node (ref "D17") (pin "1") (pinfunction "-_1") (pintype "passive"))
      (node (ref "U2") (pin "7") (pinfunction "OUT0_7") (pintype "output"))
    )
    (net (code "43") (name "Net-(D18--)") (class "Default")
      (node (ref "D18") (pin "1") (pinfunction "-_1") (pintype "passive"))
      (node (ref "U2") (pin "8") (pinfunction "OUT1_8") (pintype "output"))
    )
    (net (code "44") (name "Net-(D19--)") (class "Default")
      (node (ref "D19") (pin "1") (pinfunction "-_1") (pintype "passive"))
      (node (ref "U2") (pin "9") (pinfunction "OUT2_9") (pintype "output"))
    )
    (net (code "45") (name "Net-(D20--)") (class "Default")
      (node (ref "D20") (pin "1") (pinfunction "-_1") (pintype "passive"))
      (node (ref "U2") (pin "10") (pinfunction "OUT3_10") (pintype "output"))
    )
    (net (code "46") (name "Net-(D21--)") (class "Default")
      (node (ref "D21") (pin "1") (pinfunction "-_1") (pintype "passive"))
      (node (ref "U2") (pin "11") (pinfunction "OUT4_11") (pintype "output"))
    )
    (net (code "47") (name "Net-(D22--)") (class "Default")
      (node (ref "D22") (pin "1") (pinfunction "-_1") (pintype "passive"))
      (node (ref "U2") (pin "12") (pinfunction "OUT5_12") (pintype "output"))
    )
    (net (code "48") (name "Net-(D23--)") (class "Default")
      (node (ref "D23") (pin "1") (pinfunction "-_1") (pintype "passive"))
      (node (ref "U2") (pin "13") (pinfunction "OUT6_13") (pintype "output"))
    )
    (net (code "49") (name "Net-(D24--)") (class "Default")
      (node (ref "D24") (pin "1") (pinfunction "-_1") (pintype "passive"))
      (node (ref "U2") (pin "14") (pinfunction "OUT7_14") (pintype "output"))
    )
    (net (code "50") (name "Net-(D25--)") (class "Default")
      (node (ref "D25") (pin "1") (pinfunction "-_1") (pintype "passive"))
      (node (ref "U2") (pin "15") (pinfunction "OUT8_15") (pintype "output"))
    )
    (net (code "51") (name "Net-(D26--)") (class "Default")
      (node (ref "D26") (pin "1") (pinfunction "-_1") (pintype "passive"))
      (node (ref "U2") (pin "16") (pinfunction "OUT9_16") (pintype "output"))
    )
    (net (code "52") (name "Net-(D27--)") (class "Default")
      (node (ref "D27") (pin "1") (pinfunction "-_1") (pintype "passive"))
      (node (ref "U2") (pin "17") (pinfunction "OUT10_17") (pintype "output"))
    )
    (net (code "53") (name "Net-(D28--)") (class "Default")
      (node (ref "D28") (pin "1") (pinfunction "-_1") (pintype "passive"))
      (node (ref "U2") (pin "18") (pinfunction "OUT11_18") (pintype "output"))
    )
    (net (code "54") (name "Net-(D29--)") (class "Default")
      (node (ref "D29") (pin "1") (pinfunction "-_1") (pintype "passive"))
      (node (ref "U2") (pin "19") (pinfunction "OUT12_19") (pintype "output"))
    )
    (net (code "55") (name "Net-(D30--)") (class "Default")
      (node (ref "D30") (pin "1") (pinfunction "-_1") (pintype "passive"))
      (node (ref "U2") (pin "20") (pinfunction "OUT13_20") (pintype "output"))
    )
    (net (code "56") (name "Net-(D31--)") (class "Default")
      (node (ref "D31") (pin "1") (pinfunction "-_1") (pintype "passive"))
      (node (ref "U2") (pin "21") (pinfunction "OUT14_21") (pintype "output"))
    )
    (net (code "57") (name "Net-(D32--)") (class "Default")
      (node (ref "D32") (pin "1") (pinfunction "-_1") (pintype "passive"))
      (node (ref "U2") (pin "22") (pinfunction "OUT15_22") (pintype "output"))
    )
    (net (code "58") (name "Net-(D33--)") (class "Default")
      (node (ref "D33") (pin "1") (pinfunction "-_1") (pintype "passive"))
      (node (ref "U3") (pin "7") (pinfunction "OUT0_7") (pintype "output"))
    )
    (net (code "59") (name "Net-(D34--)") (class "Default")
      (node (ref "D34") (pin "1") (pinfunction "-_1") (pintype "passive"))
      (node (ref "U3") (pin "8") (pinfunction "OUT1_8") (pintype "output"))
    )
    (net (code "60") (name "Net-(D35--)") (class "Default")
      (node (ref "D35") (pin "1") (pinfunction "-_1") (pintype "passive"))
      (node (ref "U3") (pin "9") (pinfunction "OUT2_9") (pintype "output"))
    )
    (net (code "61") (name "Net-(D36--)") (class "Default")
      (node (ref "D36") (pin "1") (pinfunction "-_1") (pintype "passive"))
      (node (ref "U3") (pin "10") (pinfunction "OUT3_10") (pintype "output"))
    )
    (net (code "62") (name "Net-(D37--)") (class "Default")
      (node (ref "D37") (pin "1") (pinfunction "-_1") (pintype "passive"))
      (node (ref "U3") (pin "11") (pinfunction "OUT4_11") (pintype "output"))
    )
    (net (code "63") (name "Net-(D38--)") (class "Default")
      (node (ref "D38") (pin "1") (pinfunction "-_1") (pintype "passive"))
      (node (ref "U3") (pin "12") (pinfunction "OUT5_12") (pintype "output"))
    )
    (net (code "64") (name "Net-(D39--)") (class "Default")
      (node (ref "D39") (pin "1") (pinfunction "-_1") (pintype "passive"))
      (node (ref "U3") (pin "13") (pinfunction "OUT6_13") (pintype "output"))
    )
    (net (code "65") (name "Net-(D40--)") (class "Default")
      (node (ref "D40") (pin "1") (pinfunction "-_1") (pintype "passive"))
      (node (ref "U3") (pin "14") (pinfunction "OUT7_14") (pintype "output"))
    )
    (net (code "66") (name "Net-(D41--)") (class "Default")
      (node (ref "D41") (pin "1") (pinfunction "-_1") (pintype "passive"))
      (node (ref "U3") (pin "15") (pinfunction "OUT8_15") (pintype "output"))
    )
    (net (code "67") (name "Net-(D42--)") (class "Default")
      (node (ref "D42") (pin "1") (pinfunction "-_1") (pintype "passive"))
      (node (ref "U3") (pin "16") (pinfunction "OUT9_16") (pintype "output"))
    )
    (net (code "68") (name "Net-(D43--)") (class "Default")
      (node (ref "D43") (pin "1") (pinfunction "-_1") (pintype "passive"))
      (node (ref "U3") (pin "17") (pinfunction "OUT10_17") (pintype "output"))
    )
    (net (code "69") (name "Net-(D44--)") (class "Default")
      (node (ref "D44") (pin "1") (pinfunction "-_1") (pintype "passive"))
      (node (ref "U3") (pin "18") (pinfunction "OUT11_18") (pintype "output"))
    )
    (net (code "70") (name "Net-(D45--)") (class "Default")
      (node (ref "D45") (pin "1") (pinfunction "-_1") (pintype "passive"))
      (node (ref "U3") (pin "19") (pinfunction "OUT12_19") (pintype "output"))
    )
    (net (code "71") (name "Net-(D46--)") (class "Default")
      (node (ref "D46") (pin "1") (pinfunction "-_1") (pintype "passive"))
      (node (ref "U3") (pin "20") (pinfunction "OUT13_20") (pintype "output"))
    )
    (net (code "72") (name "Net-(D47--)") (class "Default")
      (node (ref "D47") (pin "1") (pinfunction "-_1") (pintype "passive"))
      (node (ref "U3") (pin "21") (pinfunction "OUT14_21") (pintype "output"))
    )
    (net (code "73") (name "Net-(D48--)") (class "Default")
      (node (ref "D48") (pin "1") (pinfunction "-_1") (pintype "passive"))
      (node (ref "U3") (pin "22") (pinfunction "OUT15_22") (pintype "output"))
    )
    (net (code "74") (name "Net-(D49--)") (class "Default")
      (node (ref "D49") (pin "1") (pinfunction "-_1") (pintype "passive"))
      (node (ref "U4") (pin "7") (pinfunction "OUT0_7") (pintype "output"))
    )
    (net (code "75") (name "Net-(D50--)") (class "Default")
      (node (ref "D50") (pin "1") (pinfunction "-_1") (pintype "passive"))
      (node (ref "U4") (pin "8") (pinfunction "OUT1_8") (pintype "output"))
    )
    (net (code "76") (name "Net-(D51--)") (class "Default")
      (node (ref "D51") (pin "1") (pinfunction "-_1") (pintype "passive"))
      (node (ref "U4") (pin "9") (pinfunction "OUT2_9") (pintype "output"))
    )
    (net (code "77") (name "Net-(D52--)") (class "Default")
      (node (ref "D52") (pin "1") (pinfunction "-_1") (pintype "passive"))
      (node (ref "U4") (pin "10") (pinfunction "OUT3_10") (pintype "output"))
    )
    (net (code "78") (name "Net-(D53--)") (class "Default")
      (node (ref "D53") (pin "1") (pinfunction "-_1") (pintype "passive"))
      (node (ref "U4") (pin "11") (pinfunction "OUT4_11") (pintype "output"))
    )
    (net (code "79") (name "Net-(D54--)") (class "Default")
      (node (ref "D54") (pin "1") (pinfunction "-_1") (pintype "passive"))
      (node (ref "U4") (pin "12") (pinfunction "OUT5_12") (pintype "output"))
    )
    (net (code "80") (name "Net-(D55--)") (class "Default")
      (node (ref "D55") (pin "1") (pinfunction "-_1") (pintype "passive"))
      (node (ref "U4") (pin "13") (pinfunction "OUT6_13") (pintype "output"))
    )
    (net (code "81") (name "Net-(D56--)") (class "Default")
      (node (ref "D56") (pin "1") (pinfunction "-_1") (pintype "passive"))
      (node (ref "U4") (pin "14") (pinfunction "OUT7_14") (pintype "output"))
    )
    (net (code "82") (name "Net-(D57--)") (class "Default")
      (node (ref "D57") (pin "1") (pinfunction "-_1") (pintype "passive"))
      (node (ref "U4") (pin "15") (pinfunction "OUT8_15") (pintype "output"))
    )
    (net (code "83") (name "Net-(D58--)") (class "Default")
      (node (ref "D58") (pin "1") (pinfunction "-_1") (pintype "passive"))
      (node (ref "U4") (pin "16") (pinfunction "OUT9_16") (pintype "output"))
    )
    (net (code "84") (name "Net-(D59--)") (class "Default")
      (node (ref "D59") (pin "1") (pinfunction "-_1") (pintype "passive"))
      (node (ref "U4") (pin "17") (pinfunction "OUT10_17") (pintype "output"))
    )
    (net (code "85") (name "Net-(D60--)") (class "Default")
      (node (ref "D60") (pin "1") (pinfunction "-_1") (pintype "passive"))
      (node (ref "U4") (pin "18") (pinfunction "OUT11_18") (pintype "output"))
    )
    (net (code "86") (name "Net-(D61--)") (class "Default")
      (node (ref "D61") (pin "1") (pinfunction "-_1") (pintype "passive"))
      (node (ref "U4") (pin "19") (pinfunction "OUT12_19") (pintype "output"))
    )
    (net (code "87") (name "Net-(D62--)") (class "Default")
      (node (ref "D62") (pin "1") (pinfunction "-_1") (pintype "passive"))
      (node (ref "U4") (pin "20") (pinfunction "OUT13_20") (pintype "output"))
    )
    (net (code "88") (name "Net-(D63--)") (class "Default")
      (node (ref "D63") (pin "1") (pinfunction "-_1") (pintype "passive"))
      (node (ref "U4") (pin "21") (pinfunction "OUT14_21") (pintype "output"))
    )
    (net (code "89") (name "Net-(D64--)") (class "Default")
      (node (ref "D64") (pin "1") (pinfunction "-_1") (pintype "passive"))
      (node (ref "U4") (pin "22") (pinfunction "OUT15_22") (pintype "output"))
    )
    (net (code "90") (name "Net-(D65-PadC)") (class "Default")
      (node (ref "D65") (pin "C") (pinfunction "C_C") (pintype "passive"))
      (node (ref "R10") (pin "2") (pinfunction "2_2") (pintype "passive"))
    )
    (net (code "91") (name "Net-(R11-Pad2)") (class "Default")
      (node (ref "R11") (pin "2") (pinfunction "2_2") (pintype "passive"))
      (node (ref "R21") (pin "1") (pinfunction "1_1") (pintype "passive"))
      (node (ref "U$4") (pin "TA") (pinfunction "TA_TA") (pintype "bidirectional"))
    )
    (net (code "92") (name "Net-(R12-Pad2)") (class "Default")
      (node (ref "R12") (pin "2") (pinfunction "2_2") (pintype "passive"))
      (node (ref "R22") (pin "1") (pinfunction "1_1") (pintype "passive"))
      (node (ref "U$4") (pin "TB") (pinfunction "TB_TB") (pintype "bidirectional"))
    )
    (net (code "93") (name "Net-(R18-Pad2)") (class "Default")
      (node (ref "R18") (pin "2") (pinfunction "2_2") (pintype "passive"))
      (node (ref "WS2") (pin "DIN") (pinfunction "DIN_DIN") (pintype "bidirectional"))
    )
    (net (code "94") (name "Net-(U1-IREF)") (class "Default")
      (node (ref "R1") (pin "2") (pinfunction "2_2") (pintype "passive"))
      (node (ref "U1") (pin "27") (pinfunction "IREF_27") (pintype "input"))
    )
    (net (code "95") (name "Net-(U1-SOUT)") (class "Default")
      (node (ref "U1") (pin "24") (pinfunction "SOUT_24") (pintype "output"))
      (node (ref "U2") (pin "5") (pinfunction "SIN_5") (pintype "input"))
    )
    (net (code "96") (name "Net-(U1-TEST)") (class "Default")
      (node (ref "R2") (pin "2") (pinfunction "2_2") (pintype "passive"))
      (node (ref "U1") (pin "26") (pinfunction "TEST_26") (pintype "input"))
    )
    (net (code "97") (name "Net-(U2-IREF)") (class "Default")
      (node (ref "R3") (pin "2") (pinfunction "2_2") (pintype "passive"))
      (node (ref "U2") (pin "27") (pinfunction "IREF_27") (pintype "input"))
    )
    (net (code "98") (name "Net-(U2-SOUT)") (class "Default")
      (node (ref "U2") (pin "24") (pinfunction "SOUT_24") (pintype "output"))
      (node (ref "U3") (pin "5") (pinfunction "SIN_5") (pintype "input"))
    )
    (net (code "99") (name "Net-(U2-TEST)") (class "Default")
      (node (ref "R4") (pin "2") (pinfunction "2_2") (pintype "passive"))
      (node (ref "U2") (pin "26") (pinfunction "TEST_26") (pintype "input"))
    )
    (net (code "100") (name "Net-(U3-IREF)") (class "Default")
      (node (ref "R5") (pin "2") (pinfunction "2_2") (pintype "passive"))
      (node (ref "U3") (pin "27") (pinfunction "IREF_27") (pintype "input"))
    )
    (net (code "101") (name "Net-(U3-SOUT)") (class "Default")
      (node (ref "U3") (pin "24") (pinfunction "SOUT_24") (pintype "output"))
      (node (ref "U4") (pin "5") (pinfunction "SIN_5") (pintype "input"))
    )
    (net (code "102") (name "Net-(U3-TEST)") (class "Default")
      (node (ref "R6") (pin "2") (pinfunction "2_2") (pintype "passive"))
      (node (ref "U3") (pin "26") (pinfunction "TEST_26") (pintype "input"))
    )
    (net (code "103") (name "Net-(U4-IREF)") (class "Default")
      (node (ref "R7") (pin "2") (pinfunction "2_2") (pintype "passive"))
      (node (ref "U4") (pin "27") (pinfunction "IREF_27") (pintype "input"))
    )
    (net (code "104") (name "Net-(U4-TEST)") (class "Default")
      (node (ref "R8") (pin "2") (pinfunction "2_2") (pintype "passive"))
      (node (ref "U4") (pin "26") (pinfunction "TEST_26") (pintype "input"))
    )
    (net (code "105") (name "Net-(U6-AREF)") (class "Default")
      (node (ref "C2") (pin "2") (pinfunction "2_2") (pintype "passive"))
      (node (ref "U6") (pin "20") (pinfunction "AREF_20") (pintype "input"))
    )
    (net (code "106") (name "Net-(U6-PB6)") (class "Default")
      (node (ref "C17") (pin "2") (pinfunction "2_2") (pintype "passive"))
      (node (ref "Q2") (pin "1") (pinfunction "1_1") (pintype "passive"))
      (node (ref "U6") (pin "7") (pinfunction "PB6_7") (pintype "bidirectional"))
    )
    (net (code "107") (name "Net-(U6-PB7)") (class "Default")
      (node (ref "C16") (pin "1") (pinfunction "1_1") (pintype "passive"))
      (node (ref "Q2") (pin "2") (pinfunction "2_2") (pintype "passive"))
      (node (ref "U6") (pin "8") (pinfunction "PB7_8") (pintype "bidirectional"))
    )
    (net (code "108") (name "Net-(WS2-PadDOUT)") (class "Default")
      (node (ref "WS2") (pin "DOUT") (pinfunction "DOUT_DOUT") (pintype "bidirectional"))
      (node (ref "WS3") (pin "DIN") (pinfunction "DIN_DIN") (pintype "bidirectional"))
    )
    (net (code "109") (name "Net-(WS3-PadDOUT)") (class "Default")
      (node (ref "WS3") (pin "DOUT") (pinfunction "DOUT_DOUT") (pintype "bidirectional"))
      (node (ref "WS4") (pin "DIN") (pinfunction "DIN_DIN") (pintype "bidirectional"))
    )
    (net (code "110") (name "Net-(WS4-PadDOUT)") (class "Default")
      (node (ref "WS4") (pin "DOUT") (pinfunction "DOUT_DOUT") (pintype "bidirectional"))
      (node (ref "WS5") (pin "DIN") (pinfunction "DIN_DIN") (pintype "bidirectional"))
    )
    (net (code "111") (name "Net-(WS5-PadDOUT)") (class "Default")
      (node (ref "WS5") (pin "DOUT") (pinfunction "DOUT_DOUT") (pintype "bidirectional"))
      (node (ref "WS6") (pin "DIN") (pinfunction "DIN_DIN") (pintype "bidirectional"))
    )
    (net (code "112") (name "Net-(WS6-PadDOUT)") (class "Default")
      (node (ref "WS6") (pin "DOUT") (pinfunction "DOUT_DOUT") (pintype "bidirectional"))
      (node (ref "WS8") (pin "DIN") (pinfunction "DIN_DIN") (pintype "bidirectional"))
    )
    (net (code "113") (name "Net-(WS8-PadDOUT)") (class "Default")
      (node (ref "WS8") (pin "DOUT") (pinfunction "DOUT_DOUT") (pintype "bidirectional"))
      (node (ref "WS9") (pin "DIN") (pinfunction "DIN_DIN") (pintype "bidirectional"))
    )
    (net (code "114") (name "Net-(WS10-PadDIN)") (class "Default")
      (node (ref "WS10") (pin "DIN") (pinfunction "DIN_DIN") (pintype "bidirectional"))
      (node (ref "WS9") (pin "DOUT") (pinfunction "DOUT_DOUT") (pintype "bidirectional"))
    )
    (net (code "115") (name "VCC") (class "Default")
      (node (ref "C1") (pin "2") (pinfunction "2_2") (pintype "passive"))
      (node (ref "C10") (pin "+") (pinfunction "+_+") (pintype "passive"))
      (node (ref "C11") (pin "+") (pinfunction "+_+") (pintype "passive"))
      (node (ref "C12") (pin "+") (pinfunction "+_+") (pintype "passive"))
      (node (ref "C13") (pin "1") (pinfunction "1_1") (pintype "passive"))
      (node (ref "C14") (pin "1") (pinfunction "1_1") (pintype "passive"))
      (node (ref "C15") (pin "1") (pinfunction "1_1") (pintype "passive"))
      (node (ref "C18") (pin "+") (pinfunction "+_+") (pintype "passive"))
      (node (ref "C20") (pin "1") (pinfunction "1_1") (pintype "passive"))
      (node (ref "C21") (pin "1") (pinfunction "1_1") (pintype "passive"))
      (node (ref "C22") (pin "1") (pinfunction "1_1") (pintype "passive"))
      (node (ref "C24") (pin "1") (pinfunction "1_1") (pintype "passive"))
      (node (ref "C25") (pin "1") (pinfunction "1_1") (pintype "passive"))
      (node (ref "C26") (pin "1") (pinfunction "1_1") (pintype "passive"))
      (node (ref "C27") (pin "1") (pinfunction "1_1") (pintype "passive"))
      (node (ref "C3") (pin "1") (pinfunction "1_1") (pintype "passive"))
      (node (ref "C4") (pin "1") (pinfunction "1_1") (pintype "passive"))
      (node (ref "C5") (pin "1") (pinfunction "1_1") (pintype "passive"))
      (node (ref "C6") (pin "1") (pinfunction "1_1") (pintype "passive"))
      (node (ref "C7") (pin "1") (pinfunction "1_1") (pintype "passive"))
      (node (ref "C8") (pin "1") (pinfunction "1_1") (pintype "passive"))
      (node (ref "C9") (pin "+") (pinfunction "+_+") (pintype "passive"))
      (node (ref "D1") (pin "2") (pinfunction "+_2") (pintype "passive"))
      (node (ref "D10") (pin "2") (pinfunction "+_2") (pintype "passive"))
      (node (ref "D11") (pin "2") (pinfunction "+_2") (pintype "passive"))
      (node (ref "D12") (pin "2") (pinfunction "+_2") (pintype "passive"))
      (node (ref "D13") (pin "2") (pinfunction "+_2") (pintype "passive"))
      (node (ref "D14") (pin "2") (pinfunction "+_2") (pintype "passive"))
      (node (ref "D15") (pin "2") (pinfunction "+_2") (pintype "passive"))
      (node (ref "D16") (pin "2") (pinfunction "+_2") (pintype "passive"))
      (node (ref "D17") (pin "2") (pinfunction "+_2") (pintype "passive"))
      (node (ref "D18") (pin "2") (pinfunction "+_2") (pintype "passive"))
      (node (ref "D19") (pin "2") (pinfunction "+_2") (pintype "passive"))
      (node (ref "D2") (pin "2") (pinfunction "+_2") (pintype "passive"))
      (node (ref "D20") (pin "2") (pinfunction "+_2") (pintype "passive"))
      (node (ref "D21") (pin "2") (pinfunction "+_2") (pintype "passive"))
      (node (ref "D22") (pin "2") (pinfunction "+_2") (pintype "passive"))
      (node (ref "D23") (pin "2") (pinfunction "+_2") (pintype "passive"))
      (node (ref "D24") (pin "2") (pinfunction "+_2") (pintype "passive"))
      (node (ref "D25") (pin "2") (pinfunction "+_2") (pintype "passive"))
      (node (ref "D26") (pin "2") (pinfunction "+_2") (pintype "passive"))
      (node (ref "D27") (pin "2") (pinfunction "+_2") (pintype "passive"))
      (node (ref "D28") (pin "2") (pinfunction "+_2") (pintype "passive"))
      (node (ref "D29") (pin "2") (pinfunction "+_2") (pintype "passive"))
      (node (ref "D3") (pin "2") (pinfunction "+_2") (pintype "passive"))
      (node (ref "D30") (pin "2") (pinfunction "+_2") (pintype "passive"))
      (node (ref "D31") (pin "2") (pinfunction "+_2") (pintype "passive"))
      (node (ref "D32") (pin "2") (pinfunction "+_2") (pintype "passive"))
      (node (ref "D33") (pin "2") (pinfunction "+_2") (pintype "passive"))
      (node (ref "D34") (pin "2") (pinfunction "+_2") (pintype "passive"))
      (node (ref "D35") (pin "2") (pinfunction "+_2") (pintype "passive"))
      (node (ref "D36") (pin "2") (pinfunction "+_2") (pintype "passive"))
      (node (ref "D37") (pin "2") (pinfunction "+_2") (pintype "passive"))
      (node (ref "D38") (pin "2") (pinfunction "+_2") (pintype "passive"))
      (node (ref "D39") (pin "2") (pinfunction "+_2") (pintype "passive"))
      (node (ref "D4") (pin "2") (pinfunction "+_2") (pintype "passive"))
      (node (ref "D40") (pin "2") (pinfunction "+_2") (pintype "passive"))
      (node (ref "D41") (pin "2") (pinfunction "+_2") (pintype "passive"))
      (node (ref "D42") (pin "2") (pinfunction "+_2") (pintype "passive"))
      (node (ref "D43") (pin "2") (pinfunction "+_2") (pintype "passive"))
      (node (ref "D44") (pin "2") (pinfunction "+_2") (pintype "passive"))
      (node (ref "D45") (pin "2") (pinfunction "+_2") (pintype "passive"))
      (node (ref "D46") (pin "2") (pinfunction "+_2") (pintype "passive"))
      (node (ref "D47") (pin "2") (pinfunction "+_2") (pintype "passive"))
      (node (ref "D48") (pin "2") (pinfunction "+_2") (pintype "passive"))
      (node (ref "D49") (pin "2") (pinfunction "+_2") (pintype "passive"))
      (node (ref "D5") (pin "2") (pinfunction "+_2") (pintype "passive"))
      (node (ref "D50") (pin "2") (pinfunction "+_2") (pintype "passive"))
      (node (ref "D51") (pin "2") (pinfunction "+_2") (pintype "passive"))
      (node (ref "D52") (pin "2") (pinfunction "+_2") (pintype "passive"))
      (node (ref "D53") (pin "2") (pinfunction "+_2") (pintype "passive"))
      (node (ref "D54") (pin "2") (pinfunction "+_2") (pintype "passive"))
      (node (ref "D55") (pin "2") (pinfunction "+_2") (pintype "passive"))
      (node (ref "D56") (pin "2") (pinfunction "+_2") (pintype "passive"))
      (node (ref "D57") (pin "2") (pinfunction "+_2") (pintype "passive"))
      (node (ref "D58") (pin "2") (pinfunction "+_2") (pintype "passive"))
      (node (ref "D59") (pin "2") (pinfunction "+_2") (pintype "passive"))
      (node (ref "D6") (pin "2") (pinfunction "+_2") (pintype "passive"))
      (node (ref "D60") (pin "2") (pinfunction "+_2") (pintype "passive"))
      (node (ref "D61") (pin "2") (pinfunction "+_2") (pintype "passive"))
      (node (ref "D62") (pin "2") (pinfunction "+_2") (pintype "passive"))
      (node (ref "D63") (pin "2") (pinfunction "+_2") (pintype "passive"))
      (node (ref "D64") (pin "2") (pinfunction "+_2") (pintype "passive"))
      (node (ref "D7") (pin "2") (pinfunction "+_2") (pintype "passive"))
      (node (ref "D8") (pin "2") (pinfunction "+_2") (pintype "passive"))
      (node (ref "D9") (pin "2") (pinfunction "+_2") (pintype "passive"))
      (node (ref "R11") (pin "1") (pinfunction "1_1") (pintype "passive"))
      (node (ref "R12") (pin "1") (pinfunction "1_1") (pintype "passive"))
      (node (ref "R13") (pin "1") (pinfunction "1_1") (pintype "passive"))
      (node (ref "R14") (pin "1") (pinfunction "1_1") (pintype "passive"))
      (node (ref "R15") (pin "1") (pinfunction "1_1") (pintype "passive"))
      (node (ref "R16") (pin "1") (pinfunction "1_1") (pintype "passive"))
      (node (ref "R17") (pin "1") (pinfunction "1_1") (pintype "passive"))
      (node (ref "R19") (pin "1") (pinfunction "1_1") (pintype "passive"))
      (node (ref "R2") (pin "1") (pinfunction "1_1") (pintype "passive"))
      (node (ref "R20") (pin "1") (pinfunction "1_1") (pintype "passive"))
      (node (ref "R4") (pin "1") (pinfunction "1_1") (pintype "passive"))
      (node (ref "R6") (pin "1") (pinfunction "1_1") (pintype "passive"))
      (node (ref "R8") (pin "1") (pinfunction "1_1") (pintype "passive"))
      (node (ref "U$2") (pin "1") (pinfunction "P$1_1") (pintype "bidirectional"))
      (node (ref "U$2") (pin "10") (pinfunction "P$10_10") (pintype "bidirectional"))
      (node (ref "U$2") (pin "7") (pinfunction "P$7_7") (pintype "bidirectional"))
      (node (ref "U$2") (pin "9") (pinfunction "P$9_9") (pintype "bidirectional"))
      (node (ref "U$3") (pin "2") (pinfunction "P$2_2") (pintype "bidirectional"))
      (node (ref "U$5") (pin "1") (pinfunction "P$1_1") (pintype "bidirectional"))
      (node (ref "U$5") (pin "2") (pinfunction "P$2_2") (pintype "bidirectional"))
      (node (ref "U1") (pin "28") (pinfunction "VCC_28") (pintype "power_in"))
      (node (ref "U2") (pin "28") (pinfunction "VCC_28") (pintype "power_in"))
      (node (ref "U3") (pin "28") (pinfunction "VCC_28") (pintype "power_in"))
      (node (ref "U4") (pin "28") (pinfunction "VCC_28") (pintype "power_in"))
      (node (ref "U6") (pin "18") (pinfunction "AVCC_18") (pintype "power_in"))
      (node (ref "U6") (pin "4") (pinfunction "VCC_2_4") (pintype "power_in"))
      (node (ref "U6") (pin "6") (pinfunction "VCC_6") (pintype "power_in"))
      (node (ref "WS10") (pin "VDD") (pinfunction "VDD_VDD") (pintype "bidirectional"))
      (node (ref "WS2") (pin "VDD") (pinfunction "VDD_VDD") (pintype "bidirectional"))
      (node (ref "WS3") (pin "VDD") (pinfunction "VDD_VDD") (pintype "bidirectional"))
      (node (ref "WS4") (pin "VDD") (pinfunction "VDD_VDD") (pintype "bidirectional"))
      (node (ref "WS5") (pin "VDD") (pinfunction "VDD_VDD") (pintype "bidirectional"))
      (node (ref "WS6") (pin "VDD") (pinfunction "VDD_VDD") (pintype "bidirectional"))
      (node (ref "WS8") (pin "VDD") (pinfunction "VDD_VDD") (pintype "bidirectional"))
      (node (ref "WS9") (pin "VDD") (pinfunction "VDD_VDD") (pintype "bidirectional"))
    )
    (net (code "116") (name "unconnected-(U1-XERR-Pad23)") (class "Default")
      (node (ref "U1") (pin "23") (pinfunction "XERR_23") (pintype "output"))
    )
    (net (code "117") (name "unconnected-(U2-XERR-Pad23)") (class "Default")
      (node (ref "U2") (pin "23") (pinfunction "XERR_23") (pintype "output"))
    )
    (net (code "118") (name "unconnected-(U3-XERR-Pad23)") (class "Default")
      (node (ref "U3") (pin "23") (pinfunction "XERR_23") (pintype "output"))
    )
    (net (code "119") (name "unconnected-(U4-SOUT-Pad24)") (class "Default")
      (node (ref "U4") (pin "24") (pinfunction "SOUT_24") (pintype "output"))
    )
    (net (code "120") (name "unconnected-(U4-XERR-Pad23)") (class "Default")
      (node (ref "U4") (pin "23") (pinfunction "XERR_23") (pintype "output"))
    )
    (net (code "121") (name "unconnected-(U6-PD5-Pad9)") (class "Default")
      (node (ref "U6") (pin "9") (pinfunction "PD5_9") (pintype "bidirectional"))
    )
    (net (code "122") (name "unconnected-(WS10-PadDOUT)") (class "Default")
      (node (ref "WS10") (pin "DOUT") (pinfunction "DOUT_DOUT") (pintype "bidirectional"))
    )
  )
)
